# xiaokey.net
KiCad netlist of a schematic drawn in EAGLE
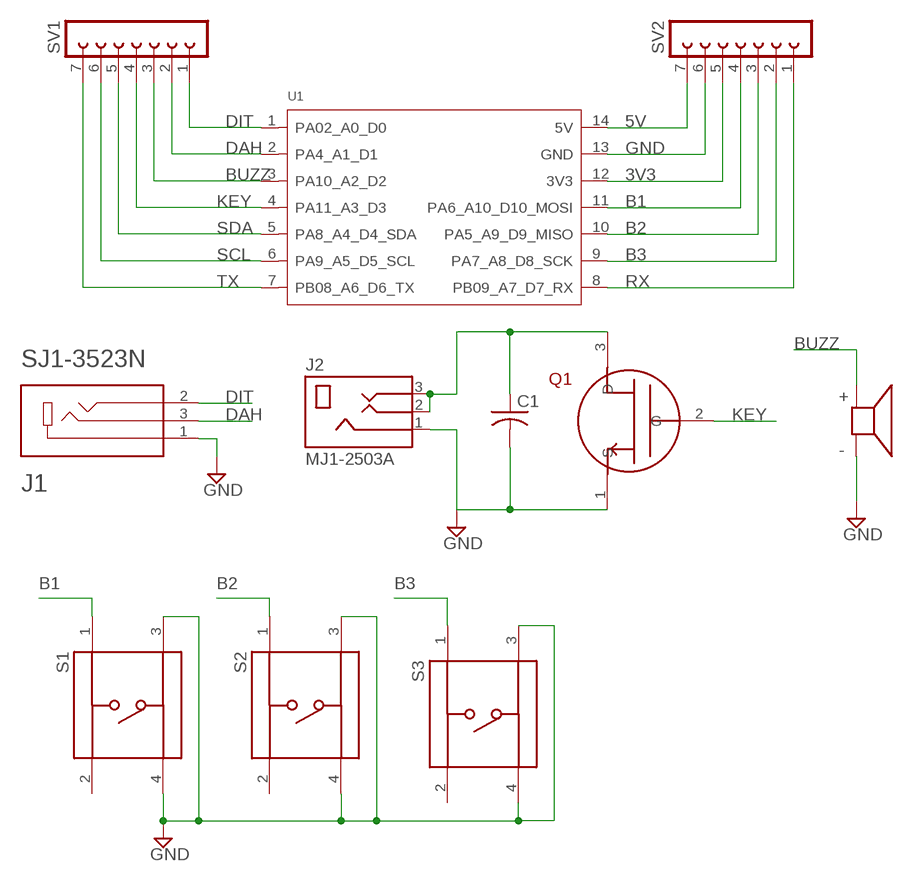
[diagram p0: schematic, sheet 1]

(export (version "E")
  (design (tool "Eeschema 10.0.6"))
  (components
    (comp (ref "C1")
      (value "C-US050-024X044")
      (footprint "eagle-import:C050-024X044")
      (libsource (lib "eagle-import") (part "C-US050-024X044"))
    )
    (comp (ref "J1")
      (value "SJ1-3523N")
      (footprint "eagle-import:CUI_SJ1-3523N")
      (fields (field (name "MF") "CUI Devices"))
      (libsource (lib "eagle-import") (part "SJ1-3523N"))
    )
    (comp (ref "J2")
      (value "MJ1-2503A")
      (footprint "eagle-import:CUI_MJ1-2503A")
      (fields (field (name "MF") "CUI Devices"))
      (libsource (lib "eagle-import") (part "MJ1-2503A"))
    )
    (comp (ref "LS1")
      (value "AT-0927-TT-6-R")
      (footprint "eagle-import:XDCR_AT-0927-TT-6-R")
      (fields (field (name "MF") "PUI Audio,"))
      (libsource (lib "eagle-import") (part "AT-0927-TT-6-R"))
    )
    (comp (ref "Q1")
      (value "2N7000")
      (footprint "eagle-import:TO92-LINE")
      (fields (field (name "MF") "STMicroelectronics"))
      (libsource (lib "eagle-import") (part "2N7000"))
    )
    (comp (ref "S1")
      (value "TS02-66-60-BK-160-LCR-D")
      (footprint "eagle-import:SW_TS02-66-60-BK-160-LCR-D")
      (fields (field (name "MF") "CUI Devices"))
      (libsource (lib "eagle-import") (part "TS02-66-60-BK-160-LCR-D"))
    )
    (comp (ref "S2")
      (value "TS02-66-60-BK-160-LCR-D")
      (footprint "eagle-import:SW_TS02-66-60-BK-160-LCR-D")
      (fields (field (name "MF") "CUI Devices"))
      (libsource (lib "eagle-import") (part "TS02-66-60-BK-160-LCR-D"))
    )
    (comp (ref "S3")
      (value "TS02-66-60-BK-160-LCR-D")
      (footprint "eagle-import:SW_TS02-66-60-BK-160-LCR-D")
      (fields (field (name "MF") "CUI Devices"))
      (libsource (lib "eagle-import") (part "TS02-66-60-BK-160-LCR-D"))
    )
    (comp (ref "SV1")
      (value "FE07-1")
      (footprint "eagle-import:FE07")
      (libsource (lib "eagle-import") (part "FE07-1"))
    )
    (comp (ref "SV2")
      (value "FE07-1")
      (footprint "eagle-import:FE07")
      (libsource (lib "eagle-import") (part "FE07-1"))
    )
    (comp (ref "U1")
      (value "MOUDLE-SEEEDUINO-XIAO")
      (footprint "eagle-import:MOUDLE14P-2.54-21X17.8MM")
      (libsource (lib "eagle-import") (part "MOUDLE-SEEEDUINO-XIAO"))
    )
  )
  (nets
    (net (code "1") (name "/3V3") (class "Default")
      (node (ref "SV2") (pin "5") (pinfunction "5_5") (pintype "passive"))
      (node (ref "U1") (pin "12") (pinfunction "3V3_12") (pintype "bidirectional"))
    )
    (net (code "2") (name "/5V") (class "Default")
      (node (ref "SV2") (pin "7") (pinfunction "7_7") (pintype "passive"))
      (node (ref "U1") (pin "14") (pinfunction "5V_14") (pintype "bidirectional"))
    )
    (net (code "3") (name "/B1") (class "Default")
      (node (ref "S1") (pin "1") (pinfunction "1_1") (pintype "passive"))
      (node (ref "SV2") (pin "4") (pinfunction "4_4") (pintype "passive"))
      (node (ref "U1") (pin "11") (pinfunction "PA6_A10_D10_MOSI_11") (pintype "bidirectional"))
    )
    (net (code "4") (name "/B2") (class "Default")
      (node (ref "S2") (pin "1") (pinfunction "1_1") (pintype "passive"))
      (node (ref "SV2") (pin "3") (pinfunction "3_3") (pintype "passive"))
      (node (ref "U1") (pin "10") (pinfunction "PA5_A9_D9_MISO_10") (pintype "bidirectional"))
    )
    (net (code "5") (name "/B3") (class "Default")
      (node (ref "S3") (pin "1") (pinfunction "1_1") (pintype "passive"))
      (node (ref "SV2") (pin "2") (pinfunction "2_2") (pintype "passive"))
      (node (ref "U1") (pin "9") (pinfunction "PA7_A8_D8_SCK_9") (pintype "bidirectional"))
    )
    (net (code "6") (name "/BUZZ") (class "Default")
      (node (ref "LS1") (pin "P") (pinfunction "P_P") (pintype "passive"))
      (node (ref "SV1") (pin "3") (pinfunction "3_3") (pintype "passive"))
      (node (ref "U1") (pin "3") (pinfunction "PA10_A2_D2_3") (pintype "bidirectional"))
    )
    (net (code "7") (name "/DAH") (class "Default")
      (node (ref "J1") (pin "3") (pinfunction "3_3") (pintype "passive"))
      (node (ref "SV1") (pin "2") (pinfunction "2_2") (pintype "passive"))
      (node (ref "U1") (pin "2") (pinfunction "PA4_A1_D1_2") (pintype "bidirectional"))
    )
    (net (code "8") (name "/DIT") (class "Default")
      (node (ref "J1") (pin "2") (pinfunction "2_2") (pintype "passive"))
      (node (ref "SV1") (pin "1") (pinfunction "1_1") (pintype "passive"))
      (node (ref "U1") (pin "1") (pinfunction "PA02_A0_D0_1") (pintype "bidirectional"))
    )
    (net (code "9") (name "/KEY") (class "Default")
      (node (ref "Q1") (pin "2") (pinfunction "G_2") (pintype "bidirectional"))
      (node (ref "SV1") (pin "4") (pinfunction "4_4") (pintype "passive"))
      (node (ref "U1") (pin "4") (pinfunction "PA11_A3_D3_4") (pintype "bidirectional"))
    )
    (net (code "10") (name "/RX") (class "Default")
      (node (ref "SV2") (pin "1") (pinfunction "1_1") (pintype "passive"))
      (node (ref "U1") (pin "8") (pinfunction "PB09_A7_D7_RX_8") (pintype "bidirectional"))
    )
    (net (code "11") (name "/SCL") (class "Default")
      (node (ref "SV1") (pin "6") (pinfunction "6_6") (pintype "passive"))
      (node (ref "U1") (pin "6") (pinfunction "PA9_A5_D5_SCL_6") (pintype "bidirectional"))
    )
    (net (code "12") (name "/SDA") (class "Default")
      (node (ref "SV1") (pin "5") (pinfunction "5_5") (pintype "passive"))
      (node (ref "U1") (pin "5") (pinfunction "PA8_A4_D4_SDA_5") (pintype "bidirectional"))
    )
    (net (code "13") (name "/TX") (class "Default")
      (node (ref "SV1") (pin "7") (pinfunction "7_7") (pintype "passive"))
      (node (ref "U1") (pin "7") (pinfunction "PB08_A6_D6_TX_7") (pintype "bidirectional"))
    )
    (net (code "14") (name "GND") (class "Default")
      (node (ref "C1") (pin "2") (pinfunction "2_2") (pintype "passive"))
      (node (ref "J1") (pin "1") (pinfunction "1_1") (pintype "passive"))
      (node (ref "J2") (pin "1") (pinfunction "1_1") (pintype "passive"))
      (node (ref "LS1") (pin "N") (pinfunction "N_N") (pintype "passive"))
      (node (ref "Q1") (pin "1") (pinfunction "S_1") (pintype "bidirectional"))
      (node (ref "S1") (pin "3") (pinfunction "3_3") (pintype "passive"))
      (node (ref "S1") (pin "4") (pinfunction "4_4") (pintype "passive"))
      (node (ref "S2") (pin "3") (pinfunction "3_3") (pintype "passive"))
      (node (ref "S2") (pin "4") (pinfunction "4_4") (pintype "passive"))
      (node (ref "S3") (pin "3") (pinfunction "3_3") (pintype "passive"))
      (node (ref "S3") (pin "4") (pinfunction "4_4") (pintype "passive"))
      (node (ref "SV2") (pin "6") (pinfunction "6_6") (pintype "passive"))
      (node (ref "U1") (pin "13") (pinfunction "GND_13") (pintype "bidirectional"))
    )
    (net (code "15") (name "Net-(Q1-D)") (class "Default")
      (node (ref "C1") (pin "1") (pinfunction "1_1") (pintype "passive"))
      (node (ref "J2") (pin "2") (pinfunction "2_2") (pintype "passive"))
      (node (ref "J2") (pin "3") (pinfunction "3_3") (pintype "passive"))
      (node (ref "Q1") (pin "3") (pinfunction "D_3") (pintype "bidirectional"))
    )
    (net (code "16") (name "unconnected-(S1-Pad2)") (class "Default")
      (node (ref "S1") (pin "2") (pinfunction "2_2") (pintype "passive"))
    )
    (net (code "17") (name "unconnected-(S2-Pad2)") (class "Default")
      (node (ref "S2") (pin "2") (pinfunction "2_2") (pintype "passive"))
    )
    (net (code "18") (name "unconnected-(S3-Pad2)") (class "Default")
      (node (ref "S3") (pin "2") (pinfunction "2_2") (pintype "passive"))
    )
  )
)
